# dual_encoder_i2c_revC.net
KiCad netlist of a schematic drawn in EAGLE
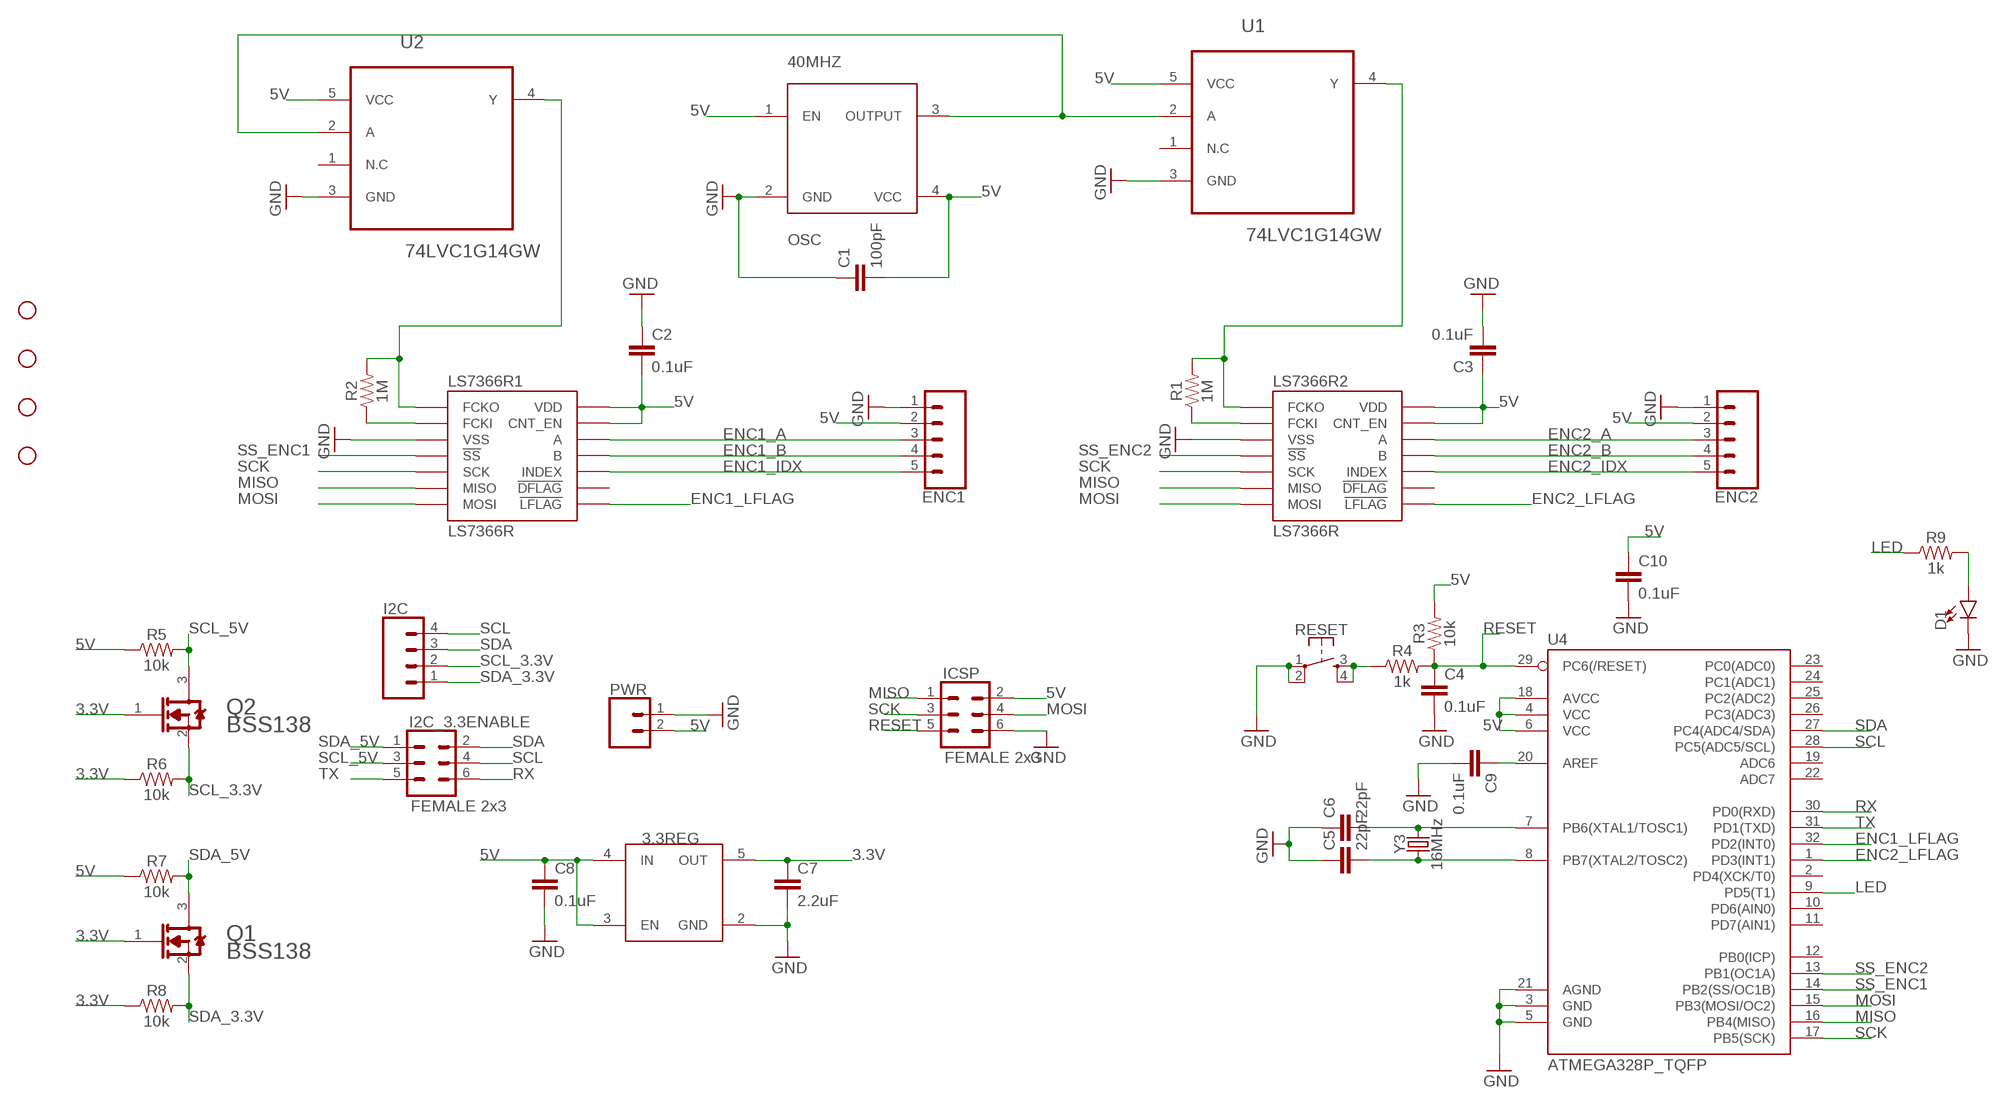
[diagram p0: schematic, sheet 1]

(export (version "E")
  (design (tool "Eeschema 10.0.6"))
  (components
    (comp (ref "3.3REG")
      (value "MIC3490-3.3YM5-TR")
      (footprint "eagle-import:SOT95P285X145-5N")
      (libsource (lib "eagle-import") (part "MIC3490-3.3YM5-TR"))
    )
    (comp (ref "40MHZ")
      (value "OSC")
      (footprint "eagle-import:CB3OSCILLATOR")
      (libsource (lib "eagle-import") (part "OSC"))
    )
    (comp (ref "C1")
      (value "100pF")
      (footprint "eagle-import:0603")
      (libsource (lib "eagle-import") (part "100PF-0603-50V-5%"))
    )
    (comp (ref "C2")
      (value "0.1uF")
      (footprint "eagle-import:0603")
      (libsource (lib "eagle-import") (part "0.1UF-0603-25V-5%"))
    )
    (comp (ref "C3")
      (value "0.1uF")
      (footprint "eagle-import:0603")
      (libsource (lib "eagle-import") (part "0.1UF-0603-25V-5%"))
    )
    (comp (ref "C4")
      (value "0.1uF")
      (footprint "eagle-import:0603")
      (libsource (lib "eagle-import") (part "0.1UF-0603-25V-5%"))
    )
    (comp (ref "C5")
      (value "22pF")
      (footprint "eagle-import:0603")
      (libsource (lib "eagle-import") (part "22PF-0603-50V-5%"))
    )
    (comp (ref "C6")
      (value "22pF")
      (footprint "eagle-import:0603")
      (libsource (lib "eagle-import") (part "22PF-0603-50V-5%"))
    )
    (comp (ref "C7")
      (value "2.2uF")
      (footprint "eagle-import:0603")
      (libsource (lib "eagle-import") (part "2.2UF-0603-10V-20%"))
    )
    (comp (ref "C8")
      (value "0.1uF")
      (footprint "eagle-import:0603")
      (libsource (lib "eagle-import") (part "0.1UF-0603-25V-5%"))
    )
    (comp (ref "C9")
      (value "0.1uF")
      (footprint "eagle-import:0603")
      (libsource (lib "eagle-import") (part "0.1UF-0603-25V-5%"))
    )
    (comp (ref "C10")
      (value "0.1uF")
      (footprint "eagle-import:0603")
      (libsource (lib "eagle-import") (part "0.1UF-0603-25V-5%"))
    )
    (comp (ref "D1")
      (value "LED0603")
      (footprint "eagle-import:LED-0603")
      (libsource (lib "eagle-import") (part "LED0603"))
    )
    (comp (ref "ENC1")
      (value "CONN_05")
      (footprint "eagle-import:1X05")
      (libsource (lib "eagle-import") (part "CONN_05"))
    )
    (comp (ref "ENC2")
      (value "CONN_05")
      (footprint "eagle-import:1X05")
      (libsource (lib "eagle-import") (part "CONN_05"))
    )
    (comp (ref "H1")
      (value "STAND-OFF")
      (footprint "eagle-import:STAND-OFF")
      (libsource (lib "eagle-import") (part "STAND-OFF"))
    )
    (comp (ref "H2")
      (value "STAND-OFF")
      (footprint "eagle-import:STAND-OFF")
      (libsource (lib "eagle-import") (part "STAND-OFF"))
    )
    (comp (ref "H3")
      (value "STAND-OFF")
      (footprint "eagle-import:STAND-OFF")
      (libsource (lib "eagle-import") (part "STAND-OFF"))
    )
    (comp (ref "H4")
      (value "STAND-OFF")
      (footprint "eagle-import:STAND-OFF")
      (libsource (lib "eagle-import") (part "STAND-OFF"))
    )
    (comp (ref "I2C")
      (value "CONN_04")
      (footprint "eagle-import:1X04")
      (libsource (lib "eagle-import") (part "CONN_04"))
    )
    (comp (ref "I2C_3.3ENABLE")
      (value "FEMALE 2x3")
      (footprint "eagle-import:2X3")
      (libsource (lib "eagle-import") (part "CONN_03X2FEMALE"))
    )
    (comp (ref "ICSP")
      (value "FEMALE 2x3")
      (footprint "eagle-import:2X3")
      (libsource (lib "eagle-import") (part "CONN_03X2FEMALE"))
    )
    (comp (ref "LS7366R1")
      (value "LS7366R")
      (footprint "eagle-import:SOIC14")
      (fields (field (name "MF") "LSI"))
      (libsource (lib "eagle-import") (part "LS7366R"))
    )
    (comp (ref "LS7366R2")
      (value "LS7366R")
      (footprint "eagle-import:SOIC14")
      (fields (field (name "MF") "LSI"))
      (libsource (lib "eagle-import") (part "LS7366R"))
    )
    (comp (ref "PWR")
      (value "CONN_02-JST-2MM-SMT")
      (footprint "eagle-import:JST-2-SMD")
      (libsource (lib "eagle-import") (part "CONN_02-JST-2MM-SMT"))
    )
    (comp (ref "Q1")
      (value "ON_SEMI_BSS138ON_SEMI_BSS138_0_0")
      (footprint "eagle-import:ON_SEMI_BSS138_0")
      (fields
        (field (name "DIGIKEY_PART_NUMBER") "BSS138CT-ND")
        (field (name "MF") "ON Semi")
        (field (name "MOUSER_PART_NUMBER") "512-BSS138")
      )
      (libsource (lib "eagle-import") (part "ON_SEMI_BSS138ON_SEMI_BSS138_0_0"))
    )
    (comp (ref "Q2")
      (value "ON_SEMI_BSS138ON_SEMI_BSS138_0_0")
      (footprint "eagle-import:ON_SEMI_BSS138_0")
      (fields
        (field (name "DIGIKEY_PART_NUMBER") "BSS138CT-ND")
        (field (name "MF") "ON Semi")
        (field (name "MOUSER_PART_NUMBER") "512-BSS138")
      )
      (libsource (lib "eagle-import") (part "ON_SEMI_BSS138ON_SEMI_BSS138_0_0"))
    )
    (comp (ref "R1")
      (value "1M")
      (footprint "eagle-import:0603")
      (libsource (lib "eagle-import") (part "1MOHM-0603-1/4W-5%"))
    )
    (comp (ref "R2")
      (value "1M")
      (footprint "eagle-import:0603")
      (libsource (lib "eagle-import") (part "1MOHM-0603-1/4W-5%"))
    )
    (comp (ref "R3")
      (value "10k")
      (footprint "eagle-import:0603")
      (libsource (lib "eagle-import") (part "10KOHM-0603-1/10W-1%"))
    )
    (comp (ref "R4")
      (value "1k")
      (footprint "eagle-import:0603")
      (libsource (lib "eagle-import") (part "1KOHM-0603-1/10W-1%"))
    )
    (comp (ref "R5")
      (value "10k")
      (footprint "eagle-import:0603")
      (libsource (lib "eagle-import") (part "10KOHM-0603-1/10W-1%"))
    )
    (comp (ref "R6")
      (value "10k")
      (footprint "eagle-import:0603")
      (libsource (lib "eagle-import") (part "10KOHM-0603-1/10W-1%"))
    )
    (comp (ref "R7")
      (value "10k")
      (footprint "eagle-import:0603")
      (libsource (lib "eagle-import") (part "10KOHM-0603-1/10W-1%"))
    )
    (comp (ref "R8")
      (value "10k")
      (footprint "eagle-import:0603")
      (libsource (lib "eagle-import") (part "10KOHM-0603-1/10W-1%"))
    )
    (comp (ref "R9")
      (value "1k")
      (footprint "eagle-import:0603")
      (libsource (lib "eagle-import") (part "1KOHM-0603-1/10W-1%"))
    )
    (comp (ref "RESET")
      (value "MOMENTARY-SWITCH-SPST-2-SMD-5.2MM")
      (footprint "eagle-import:TACTILE_SWITCH_SMD_5.2MM")
      (libsource (lib "eagle-import") (part "MOMENTARY-SWITCH-SPST-2-SMD-5.2MM"))
    )
    (comp (ref "U1")
      (value "74LVC1G14GW")
      (footprint "eagle-import:SOT65P210X110-5N")
      (fields (field (name "MF") "NXP Semiconductors"))
      (libsource (lib "eagle-import") (part "74LVC1G14GW"))
    )
    (comp (ref "U2")
      (value "74LVC1G14GW")
      (footprint "eagle-import:SOT65P210X110-5N")
      (fields (field (name "MF") "NXP Semiconductors"))
      (libsource (lib "eagle-import") (part "74LVC1G14GW"))
    )
    (comp (ref "U4")
      (value "ATMEGA328P_TQFP")
      (footprint "eagle-import:TQFP32-08")
      (libsource (lib "eagle-import") (part "ATMEGA328P_TQFP"))
    )
    (comp (ref "Y3")
      (value "16MHz")
      (footprint "eagle-import:CRYSTAL-SMD-5X3.2-4PAD")
      (libsource (lib "eagle-import") (part "CRYSTAL-16MHZSMD-5X3.2"))
    )
  )
  (nets
    (net (code "1") (name "/3.3V") (class "Default")
      (node (ref "3.3REG") (pin "5") (pinfunction "OUT_5") (pintype "output"))
      (node (ref "C7") (pin "1") (pinfunction "1_1") (pintype "passive"))
      (node (ref "Q1") (pin "1") (pinfunction "G_1") (pintype "bidirectional"))
      (node (ref "Q2") (pin "1") (pinfunction "G_1") (pintype "bidirectional"))
      (node (ref "R6") (pin "1") (pinfunction "1_1") (pintype "passive"))
      (node (ref "R8") (pin "1") (pinfunction "1_1") (pintype "passive"))
    )
    (net (code "2") (name "/5V") (class "Default")
      (node (ref "3.3REG") (pin "3") (pinfunction "EN_3") (pintype "input"))
      (node (ref "3.3REG") (pin "4") (pinfunction "IN_4") (pintype "input"))
      (node (ref "40MHZ") (pin "1") (pinfunction "EN_1") (pintype "input"))
      (node (ref "40MHZ") (pin "4") (pinfunction "VCC_4") (pintype "input"))
      (node (ref "C1") (pin "2") (pinfunction "2_2") (pintype "passive"))
      (node (ref "C10") (pin "1") (pinfunction "1_1") (pintype "passive"))
      (node (ref "C2") (pin "2") (pinfunction "2_2") (pintype "passive"))
      (node (ref "C3") (pin "1") (pinfunction "1_1") (pintype "passive"))
      (node (ref "C8") (pin "1") (pinfunction "1_1") (pintype "passive"))
      (node (ref "ENC1") (pin "2") (pinfunction "2_2") (pintype "passive"))
      (node (ref "ENC2") (pin "2") (pinfunction "2_2") (pintype "passive"))
      (node (ref "ICSP") (pin "2") (pinfunction "2_2") (pintype "bidirectional"))
      (node (ref "LS7366R1") (pin "13") (pinfunction "CNT_EN_13") (pintype "bidirectional"))
      (node (ref "LS7366R1") (pin "14") (pinfunction "VDD_14") (pintype "bidirectional"))
      (node (ref "LS7366R2") (pin "13") (pinfunction "CNT_EN_13") (pintype "bidirectional"))
      (node (ref "LS7366R2") (pin "14") (pinfunction "VDD_14") (pintype "bidirectional"))
      (node (ref "PWR") (pin "2") (pinfunction "1_2") (pintype "passive"))
      (node (ref "R3") (pin "2") (pinfunction "2_2") (pintype "passive"))
      (node (ref "R5") (pin "1") (pinfunction "1_1") (pintype "passive"))
      (node (ref "R7") (pin "1") (pinfunction "1_1") (pintype "passive"))
      (node (ref "U1") (pin "5") (pinfunction "VCC_5") (pintype "power_in"))
      (node (ref "U2") (pin "5") (pinfunction "VCC_5") (pintype "power_in"))
      (node (ref "U4") (pin "18") (pinfunction "AVCC_18") (pintype "bidirectional"))
      (node (ref "U4") (pin "4") (pinfunction "VCC_4") (pintype "bidirectional"))
      (node (ref "U4") (pin "6") (pinfunction "VCC_6") (pintype "bidirectional"))
    )
    (net (code "3") (name "/ENC1_A") (class "Default")
      (node (ref "ENC1") (pin "3") (pinfunction "3_3") (pintype "passive"))
      (node (ref "LS7366R1") (pin "12") (pinfunction "A_12") (pintype "bidirectional"))
    )
    (net (code "4") (name "/ENC1_B") (class "Default")
      (node (ref "ENC1") (pin "4") (pinfunction "4_4") (pintype "passive"))
      (node (ref "LS7366R1") (pin "11") (pinfunction "B_11") (pintype "bidirectional"))
    )
    (net (code "5") (name "/ENC1_IDX") (class "Default")
      (node (ref "ENC1") (pin "5") (pinfunction "5_5") (pintype "passive"))
      (node (ref "LS7366R1") (pin "10") (pinfunction "INDEX_10") (pintype "bidirectional"))
    )
    (net (code "6") (name "/ENC1_LFLAG") (class "Default")
      (node (ref "LS7366R1") (pin "8") (pinfunction "~{LFLAG}_8") (pintype "bidirectional"))
      (node (ref "U4") (pin "32") (pinfunction "PD2(INT0)_32") (pintype "bidirectional"))
    )
    (net (code "7") (name "/ENC2_A") (class "Default")
      (node (ref "ENC2") (pin "3") (pinfunction "3_3") (pintype "passive"))
      (node (ref "LS7366R2") (pin "12") (pinfunction "A_12") (pintype "bidirectional"))
    )
    (net (code "8") (name "/ENC2_B") (class "Default")
      (node (ref "ENC2") (pin "4") (pinfunction "4_4") (pintype "passive"))
      (node (ref "LS7366R2") (pin "11") (pinfunction "B_11") (pintype "bidirectional"))
    )
    (net (code "9") (name "/ENC2_IDX") (class "Default")
      (node (ref "ENC2") (pin "5") (pinfunction "5_5") (pintype "passive"))
      (node (ref "LS7366R2") (pin "10") (pinfunction "INDEX_10") (pintype "bidirectional"))
    )
    (net (code "10") (name "/ENC2_LFLAG") (class "Default")
      (node (ref "LS7366R2") (pin "8") (pinfunction "~{LFLAG}_8") (pintype "bidirectional"))
      (node (ref "U4") (pin "1") (pinfunction "PD3(INT1)_1") (pintype "bidirectional"))
    )
    (net (code "11") (name "/LED") (class "Default")
      (node (ref "R9") (pin "1") (pinfunction "1_1") (pintype "passive"))
      (node (ref "U4") (pin "9") (pinfunction "PD5(T1)_9") (pintype "bidirectional"))
    )
    (net (code "12") (name "/MISO") (class "Default")
      (node (ref "ICSP") (pin "1") (pinfunction "1_1") (pintype "bidirectional"))
      (node (ref "LS7366R1") (pin "6") (pinfunction "MISO_6") (pintype "bidirectional"))
      (node (ref "LS7366R2") (pin "6") (pinfunction "MISO_6") (pintype "bidirectional"))
      (node (ref "U4") (pin "16") (pinfunction "PB4(MISO)_16") (pintype "bidirectional"))
    )
    (net (code "13") (name "/MOSI") (class "Default")
      (node (ref "ICSP") (pin "4") (pinfunction "4_4") (pintype "bidirectional"))
      (node (ref "LS7366R1") (pin "7") (pinfunction "MOSI_7") (pintype "bidirectional"))
      (node (ref "LS7366R2") (pin "7") (pinfunction "MOSI_7") (pintype "bidirectional"))
      (node (ref "U4") (pin "15") (pinfunction "PB3(MOSI/OC2)_15") (pintype "bidirectional"))
    )
    (net (code "14") (name "/RESET") (class "Default")
      (node (ref "C4") (pin "1") (pinfunction "1_1") (pintype "passive"))
      (node (ref "ICSP") (pin "5") (pinfunction "5_5") (pintype "bidirectional"))
      (node (ref "R3") (pin "1") (pinfunction "1_1") (pintype "passive"))
      (node (ref "R4") (pin "2") (pinfunction "2_2") (pintype "passive"))
      (node (ref "U4") (pin "29") (pinfunction "PC6(/RESET)_29") (pintype "bidirectional"))
    )
    (net (code "15") (name "/RX") (class "Default")
      (node (ref "I2C_3.3ENABLE") (pin "6") (pinfunction "6_6") (pintype "bidirectional"))
      (node (ref "U4") (pin "30") (pinfunction "PD0(RXD)_30") (pintype "bidirectional"))
    )
    (net (code "16") (name "/SCK") (class "Default")
      (node (ref "ICSP") (pin "3") (pinfunction "3_3") (pintype "bidirectional"))
      (node (ref "LS7366R1") (pin "5") (pinfunction "SCK_5") (pintype "bidirectional"))
      (node (ref "LS7366R2") (pin "5") (pinfunction "SCK_5") (pintype "bidirectional"))
      (node (ref "U4") (pin "17") (pinfunction "PB5(SCK)_17") (pintype "bidirectional"))
    )
    (net (code "17") (name "/SCL") (class "Default")
      (node (ref "I2C") (pin "4") (pinfunction "4_4") (pintype "passive"))
      (node (ref "I2C_3.3ENABLE") (pin "4") (pinfunction "4_4") (pintype "bidirectional"))
      (node (ref "U4") (pin "28") (pinfunction "PC5(ADC5/SCL)_28") (pintype "bidirectional"))
    )
    (net (code "18") (name "/SCL_3.3V") (class "Default")
      (node (ref "I2C") (pin "2") (pinfunction "2_2") (pintype "passive"))
      (node (ref "Q2") (pin "2") (pinfunction "S_2") (pintype "bidirectional"))
      (node (ref "R6") (pin "2") (pinfunction "2_2") (pintype "passive"))
    )
    (net (code "19") (name "/SCL_5V") (class "Default")
      (node (ref "I2C_3.3ENABLE") (pin "3") (pinfunction "3_3") (pintype "bidirectional"))
      (node (ref "Q2") (pin "3") (pinfunction "D_3") (pintype "bidirectional"))
      (node (ref "R5") (pin "2") (pinfunction "2_2") (pintype "passive"))
    )
    (net (code "20") (name "/SDA") (class "Default")
      (node (ref "I2C") (pin "3") (pinfunction "3_3") (pintype "passive"))
      (node (ref "I2C_3.3ENABLE") (pin "2") (pinfunction "2_2") (pintype "bidirectional"))
      (node (ref "U4") (pin "27") (pinfunction "PC4(ADC4/SDA)_27") (pintype "bidirectional"))
    )
    (net (code "21") (name "/SDA_3.3V") (class "Default")
      (node (ref "I2C") (pin "1") (pinfunction "1_1") (pintype "passive"))
      (node (ref "Q1") (pin "2") (pinfunction "S_2") (pintype "bidirectional"))
      (node (ref "R8") (pin "2") (pinfunction "2_2") (pintype "passive"))
    )
    (net (code "22") (name "/SDA_5V") (class "Default")
      (node (ref "I2C_3.3ENABLE") (pin "1") (pinfunction "1_1") (pintype "bidirectional"))
      (node (ref "Q1") (pin "3") (pinfunction "D_3") (pintype "bidirectional"))
      (node (ref "R7") (pin "2") (pinfunction "2_2") (pintype "passive"))
    )
    (net (code "23") (name "/SS_ENC1") (class "Default")
      (node (ref "LS7366R1") (pin "4") (pinfunction "~{SS}_4") (pintype "bidirectional"))
      (node (ref "U4") (pin "14") (pinfunction "PB2(SS/OC1B)_14") (pintype "bidirectional"))
    )
    (net (code "24") (name "/SS_ENC2") (class "Default")
      (node (ref "LS7366R2") (pin "4") (pinfunction "~{SS}_4") (pintype "bidirectional"))
      (node (ref "U4") (pin "13") (pinfunction "PB1(OC1A)_13") (pintype "bidirectional"))
    )
    (net (code "25") (name "/TX") (class "Default")
      (node (ref "I2C_3.3ENABLE") (pin "5") (pinfunction "5_5") (pintype "bidirectional"))
      (node (ref "U4") (pin "31") (pinfunction "PD1(TXD)_31") (pintype "bidirectional"))
    )
    (net (code "26") (name "GND") (class "Default")
      (node (ref "3.3REG") (pin "2") (pinfunction "GND_2") (pintype "bidirectional"))
      (node (ref "40MHZ") (pin "2") (pinfunction "GND_2") (pintype "input"))
      (node (ref "C1") (pin "1") (pinfunction "1_1") (pintype "passive"))
      (node (ref "C10") (pin "2") (pinfunction "2_2") (pintype "passive"))
      (node (ref "C2") (pin "1") (pinfunction "1_1") (pintype "passive"))
      (node (ref "C3") (pin "2") (pinfunction "2_2") (pintype "passive"))
      (node (ref "C4") (pin "2") (pinfunction "2_2") (pintype "passive"))
      (node (ref "C5") (pin "1") (pinfunction "1_1") (pintype "passive"))
      (node (ref "C6") (pin "1") (pinfunction "1_1") (pintype "passive"))
      (node (ref "C7") (pin "2") (pinfunction "2_2") (pintype "passive"))
      (node (ref "C8") (pin "2") (pinfunction "2_2") (pintype "passive"))
      (node (ref "C9") (pin "2") (pinfunction "2_2") (pintype "passive"))
      (node (ref "D1") (pin "C") (pinfunction "C_C") (pintype "passive"))
      (node (ref "ENC1") (pin "1") (pinfunction "1_1") (pintype "passive"))
      (node (ref "ENC2") (pin "1") (pinfunction "1_1") (pintype "passive"))
      (node (ref "ICSP") (pin "6") (pinfunction "6_6") (pintype "bidirectional"))
      (node (ref "LS7366R1") (pin "3") (pinfunction "VSS_3") (pintype "bidirectional"))
      (node (ref "LS7366R2") (pin "3") (pinfunction "VSS_3") (pintype "bidirectional"))
      (node (ref "PWR") (pin "1") (pinfunction "2_1") (pintype "passive"))
      (node (ref "RESET") (pin "1") (pinfunction "1_1") (pintype "passive"))
      (node (ref "RESET") (pin "2") (pinfunction "2_2") (pintype "passive"))
      (node (ref "U1") (pin "3") (pinfunction "GND_3") (pintype "passive"))
      (node (ref "U2") (pin "3") (pinfunction "GND_3") (pintype "passive"))
      (node (ref "U4") (pin "21") (pinfunction "AGND_21") (pintype "bidirectional"))
      (node (ref "U4") (pin "3") (pinfunction "GND_3") (pintype "bidirectional"))
      (node (ref "U4") (pin "5") (pinfunction "GND_5") (pintype "bidirectional"))
    )
    (net (code "27") (name "Net-(40MHZ-OUTPUT)") (class "Default")
      (node (ref "40MHZ") (pin "3") (pinfunction "OUTPUT_3") (pintype "output"))
      (node (ref "U1") (pin "2") (pinfunction "A_2") (pintype "input"))
      (node (ref "U2") (pin "2") (pinfunction "A_2") (pintype "input"))
    )
    (net (code "28") (name "Net-(D1-PadA)") (class "Default")
      (node (ref "D1") (pin "A") (pinfunction "A_A") (pintype "passive"))
      (node (ref "R9") (pin "2") (pinfunction "2_2") (pintype "passive"))
    )
    (net (code "29") (name "Net-(LS7366R1-FCKI)") (class "Default")
      (node (ref "LS7366R1") (pin "2") (pinfunction "FCKI_2") (pintype "bidirectional"))
      (node (ref "R2") (pin "1") (pinfunction "1_1") (pintype "passive"))
    )
    (net (code "30") (name "Net-(LS7366R1-FCKO)") (class "Default")
      (node (ref "LS7366R1") (pin "1") (pinfunction "FCKO_1") (pintype "bidirectional"))
      (node (ref "R2") (pin "2") (pinfunction "2_2") (pintype "passive"))
      (node (ref "U2") (pin "4") (pinfunction "Y_4") (pintype "output"))
    )
    (net (code "31") (name "Net-(LS7366R2-FCKI)") (class "Default")
      (node (ref "LS7366R2") (pin "2") (pinfunction "FCKI_2") (pintype "bidirectional"))
      (node (ref "R1") (pin "1") (pinfunction "1_1") (pintype "passive"))
    )
    (net (code "32") (name "Net-(LS7366R2-FCKO)") (class "Default")
      (node (ref "LS7366R2") (pin "1") (pinfunction "FCKO_1") (pintype "bidirectional"))
      (node (ref "R1") (pin "2") (pinfunction "2_2") (pintype "passive"))
      (node (ref "U1") (pin "4") (pinfunction "Y_4") (pintype "output"))
    )
    (net (code "33") (name "Net-(R4-Pad1)") (class "Default")
      (node (ref "R4") (pin "1") (pinfunction "1_1") (pintype "passive"))
      (node (ref "RESET") (pin "3") (pinfunction "3_3") (pintype "passive"))
      (node (ref "RESET") (pin "4") (pinfunction "4_4") (pintype "passive"))
    )
    (net (code "34") (name "Net-(U4-AREF)") (class "Default")
      (node (ref "C9") (pin "1") (pinfunction "1_1") (pintype "passive"))
      (node (ref "U4") (pin "20") (pinfunction "AREF_20") (pintype "bidirectional"))
    )
    (net (code "35") (name "Net-(U4-PB6(XTAL1{slash}TOSC1))") (class "Default")
      (node (ref "C6") (pin "2") (pinfunction "2_2") (pintype "passive"))
      (node (ref "U4") (pin "7") (pinfunction "PB6(XTAL1/TOSC1)_7") (pintype "bidirectional"))
      (node (ref "Y3") (pin "3") (pinfunction "2_3") (pintype "passive"))
    )
    (net (code "36") (name "Net-(U4-PB7(XTAL2{slash}TOSC2))") (class "Default")
      (node (ref "C5") (pin "2") (pinfunction "2_2") (pintype "passive"))
      (node (ref "U4") (pin "8") (pinfunction "PB7(XTAL2/TOSC2)_8") (pintype "bidirectional"))
      (node (ref "Y3") (pin "1") (pinfunction "1_1") (pintype "passive"))
    )
    (net (code "37") (name "unconnected-(LS7366R1-~{DFLAG}-Pad9)") (class "Default")
      (node (ref "LS7366R1") (pin "9") (pinfunction "~{DFLAG}_9") (pintype "bidirectional"))
    )
    (net (code "38") (name "unconnected-(LS7366R2-~{DFLAG}-Pad9)") (class "Default")
      (node (ref "LS7366R2") (pin "9") (pinfunction "~{DFLAG}_9") (pintype "bidirectional"))
    )
    (net (code "39") (name "unconnected-(U1-N.C-Pad1)") (class "Default")
      (node (ref "U1") (pin "1") (pinfunction "N.C_1") (pintype "no_connect"))
    )
    (net (code "40") (name "unconnected-(U2-N.C-Pad1)") (class "Default")
      (node (ref "U2") (pin "1") (pinfunction "N.C_1") (pintype "no_connect"))
    )
    (net (code "41") (name "unconnected-(U4-ADC6-Pad19)") (class "Default")
      (node (ref "U4") (pin "19") (pinfunction "ADC6_19") (pintype "bidirectional"))
    )
    (net (code "42") (name "unconnected-(U4-ADC7-Pad22)") (class "Default")
      (node (ref "U4") (pin "22") (pinfunction "ADC7_22") (pintype "bidirectional"))
    )
    (net (code "43") (name "unconnected-(U4-PB0(ICP)-Pad12)") (class "Default")
      (node (ref "U4") (pin "12") (pinfunction "PB0(ICP)_12") (pintype "bidirectional"))
    )
    (net (code "44") (name "unconnected-(U4-PC0(ADC0)-Pad23)") (class "Default")
      (node (ref "U4") (pin "23") (pinfunction "PC0(ADC0)_23") (pintype "bidirectional"))
    )
    (net (code "45") (name "unconnected-(U4-PC1(ADC1)-Pad24)") (class "Default")
      (node (ref "U4") (pin "24") (pinfunction "PC1(ADC1)_24") (pintype "bidirectional"))
    )
    (net (code "46") (name "unconnected-(U4-PC2(ADC2)-Pad25)") (class "Default")
      (node (ref "U4") (pin "25") (pinfunction "PC2(ADC2)_25") (pintype "bidirectional"))
    )
    (net (code "47") (name "unconnected-(U4-PC3(ADC3)-Pad26)") (class "Default")
      (node (ref "U4") (pin "26") (pinfunction "PC3(ADC3)_26") (pintype "bidirectional"))
    )
    (net (code "48") (name "unconnected-(U4-PD4(XCK{slash}T0)-Pad2)") (class "Default")
      (node (ref "U4") (pin "2") (pinfunction "PD4(XCK/T0)_2") (pintype "bidirectional"))
    )
    (net (code "49") (name "unconnected-(U4-PD6(AIN0)-Pad10)") (class "Default")
      (node (ref "U4") (pin "10") (pinfunction "PD6(AIN0)_10") (pintype "bidirectional"))
    )
    (net (code "50") (name "unconnected-(U4-PD7(AIN1)-Pad11)") (class "Default")
      (node (ref "U4") (pin "11") (pinfunction "PD7(AIN1)_11") (pintype "bidirectional"))
    )
  )
)
